# Simultaneous_RFID_Tag_Reader.net
KiCad netlist of a schematic drawn in EAGLE
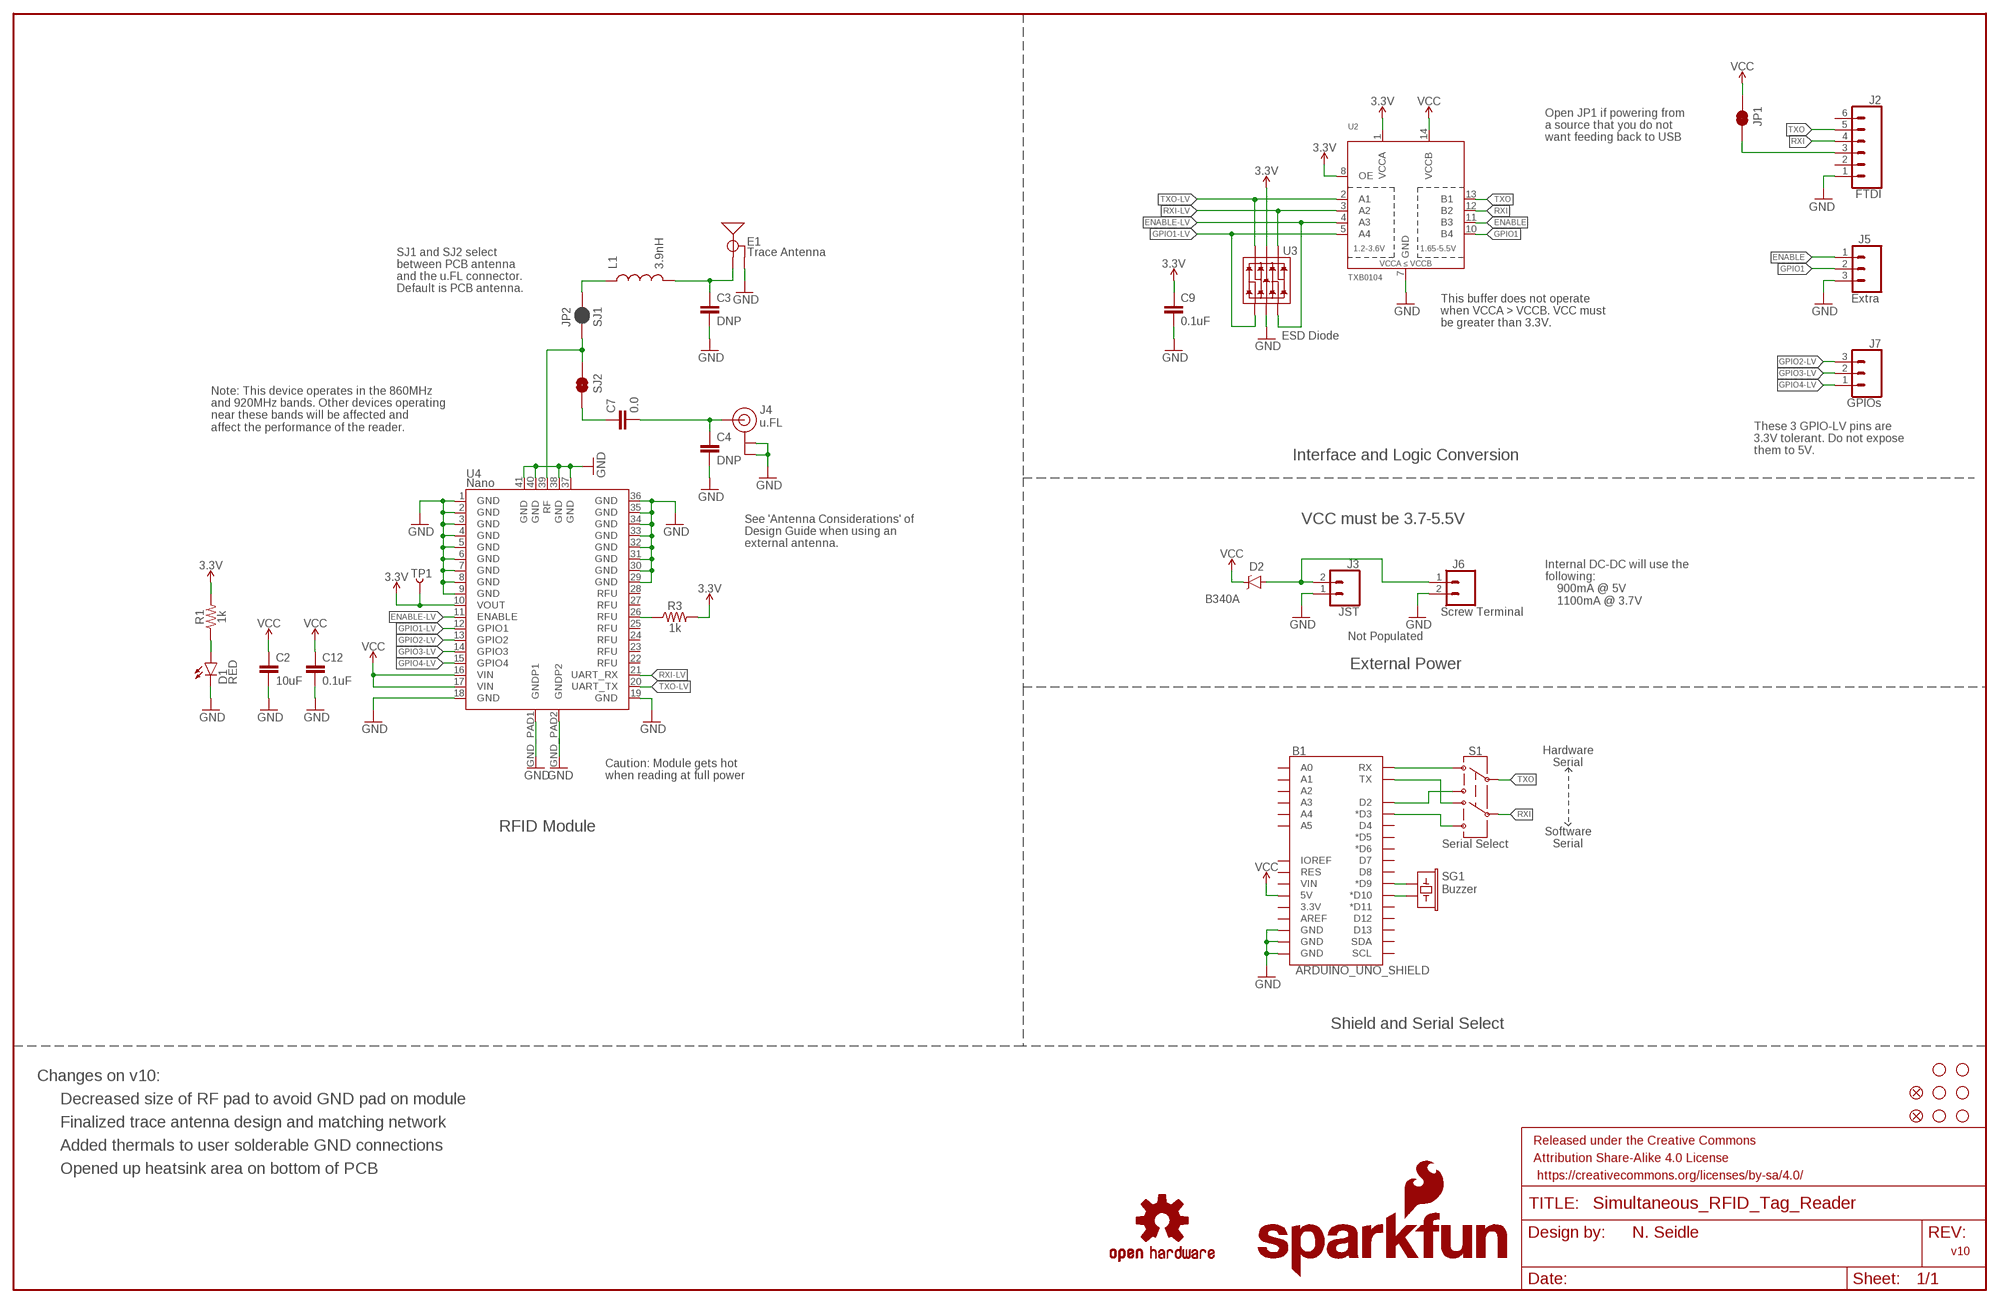
[diagram p0: schematic, sheet 1]

(export (version "E")
  (design (tool "Eeschema 10.0.6"))
  (components
    (comp (ref "B1")
      (value "ARDUINO_UNO_SHIELD")
      (footprint "eagle-import:UNO_R3_SHIELD")
      (libsource (lib "eagle-import") (part "ARDUINO_UNO_R3_SHIELDBASIC"))
    )
    (comp (ref "C2")
      (value "10uF")
      (footprint "eagle-import:0805")
      (libsource (lib "eagle-import") (part "10UF-0805-10V-10%"))
    )
    (comp (ref "C3")
      (value "DNP")
      (footprint "eagle-import:0603")
      (libsource (lib "eagle-import") (part "1.0PF-0603-50V-25%"))
    )
    (comp (ref "C4")
      (value "DNP")
      (footprint "eagle-import:0603")
      (libsource (lib "eagle-import") (part "1.0PF-0603-50V-25%"))
    )
    (comp (ref "C7")
      (value "0.0")
      (footprint "eagle-import:0603")
      (libsource (lib "eagle-import") (part "1.0PF-0603-50V-25%"))
    )
    (comp (ref "C9")
      (value "0.1uF")
      (footprint "eagle-import:0603")
      (libsource (lib "eagle-import") (part "0.1UF-0603-25V-(+80/-20%)"))
    )
    (comp (ref "C12")
      (value "0.1uF")
      (footprint "eagle-import:0603")
      (libsource (lib "eagle-import") (part "0.1UF-0603-25V-(+80/-20%)"))
    )
    (comp (ref "D1")
      (value "RED")
      (footprint "eagle-import:LED-0603")
      (libsource (lib "eagle-import") (part "LED-RED0603"))
    )
    (comp (ref "D2")
      (value "B340A")
      (footprint "eagle-import:SMA-DIODE")
      (libsource (lib "eagle-import") (part "DIODE-SCHOTTKY-B340A"))
    )
    (comp (ref "E1")
      (value "Trace Antenna")
      (footprint "eagle-import:915MHZ_ANTENNA_TRIMBLE")
      (libsource (lib "eagle-import") (part "ANTENNA_GROUNDED1"))
    )
    (comp (ref "FID1")
      (value "FIDUCIAL1X2")
      (footprint "eagle-import:FIDUCIAL-1X2")
      (libsource (lib "eagle-import") (part "FIDUCIAL1X2"))
    )
    (comp (ref "FID2")
      (value "FIDUCIAL1X2")
      (footprint "eagle-import:FIDUCIAL-1X2")
      (libsource (lib "eagle-import") (part "FIDUCIAL1X2"))
    )
    (comp (ref "FRAME1")
      (value "FRAME-LEDGER")
      (footprint "eagle-import:CREATIVE_COMMONS")
      (libsource (lib "eagle-import") (part "FRAME-LEDGER"))
    )
    (comp (ref "J2")
      (value "FTDI")
      (footprint "eagle-import:1X06")
      (libsource (lib "eagle-import") (part "CONN_06SILK_FEMALE_PTH"))
    )
    (comp (ref "J3")
      (value "JST")
      (footprint "eagle-import:JST-2-PTH")
      (libsource (lib "eagle-import") (part "CONN_02JST-PTH-2"))
    )
    (comp (ref "J4")
      (value "U.FL")
      (footprint "eagle-import:U.FL")
      (libsource (lib "eagle-import") (part "U.FL"))
    )
    (comp (ref "J5")
      (value "Extra")
      (footprint "eagle-import:1X03")
      (libsource (lib "eagle-import") (part "CONN_03"))
    )
    (comp (ref "J6")
      (value "Screw Terminal")
      (footprint "eagle-import:SCREWTERMINAL-3.5MM-2")
      (libsource (lib "eagle-import") (part "CONN_023.5MM"))
    )
    (comp (ref "J7")
      (value "GPIOs")
      (footprint "eagle-import:1X03")
      (libsource (lib "eagle-import") (part "CONN_03"))
    )
    (comp (ref "JP1")
      (value "JUMPER-SMT_2_NC_TRACE_SILK")
      (footprint "eagle-import:SMT-JUMPER_2_NC_TRACE_SILK")
      (libsource (lib "eagle-import") (part "JUMPER-SMT_2_NC_TRACE_SILK"))
    )
    (comp (ref "JP2")
      (value "SJ1")
      (footprint "eagle-import:SMT-JUMPER_2_NO_NO-SILK")
      (libsource (lib "eagle-import") (part "JUMPER-SMT_2_NO_NO-SILK"))
    )
    (comp (ref "L1")
      (value "3.9nH")
      (footprint "eagle-import:0603")
      (libsource (lib "eagle-import") (part "3.9NH_-+0.3NH_300MA(0603)0603"))
    )
    (comp (ref "LOGO1")
      (value "SFE_LOGO_NAME_FLAME.1_INCH")
      (footprint "eagle-import:SFE_LOGO_NAME_FLAME_.1")
      (libsource (lib "eagle-import") (part "SFE_LOGO_NAME_FLAME.1_INCH"))
    )
    (comp (ref "LOGO2")
      (value "OSHW-LOGOS")
      (footprint "eagle-import:OSHW-LOGO-S")
      (libsource (lib "eagle-import") (part "OSHW-LOGOS"))
    )
    (comp (ref "LOGO3")
      (value "SFE_LOGO_NAME_FLAME.1_INCH")
      (footprint "eagle-import:SFE_LOGO_NAME_FLAME_.1")
      (libsource (lib "eagle-import") (part "SFE_LOGO_NAME_FLAME.1_INCH"))
    )
    (comp (ref "R1")
      (value "1k")
      (footprint "eagle-import:0603")
      (libsource (lib "eagle-import") (part "1KOHM-0603-1/10W-1%"))
    )
    (comp (ref "R3")
      (value "1k")
      (footprint "eagle-import:0603")
      (libsource (lib "eagle-import") (part "1KOHM-0603-1/10W-1%"))
    )
    (comp (ref "S1")
      (value "Serial Select")
      (footprint "eagle-import:SWITCH_DPDT_SMD_AYZ0202")
      (libsource (lib "eagle-import") (part "SWITCH-DPDT-SMD-AYZ0202"))
    )
    (comp (ref "SG1")
      (value "Buzzer")
      (footprint "eagle-import:BUZZER-CCV")
      (libsource (lib "eagle-import") (part "BUZZERSMD2"))
    )
    (comp (ref "SJ2")
      (value "JUMPER-SMT_2_NO_NO-SILK")
      (footprint "eagle-import:SMT-JUMPER_2_NO_NO-SILK")
      (libsource (lib "eagle-import") (part "JUMPER-SMT_2_NO_NO-SILK"))
    )
    (comp (ref "STANDOFF1")
      (value "STAND-OFF")
      (footprint "eagle-import:STAND-OFF")
      (libsource (lib "eagle-import") (part "STAND-OFF"))
    )
    (comp (ref "STANDOFF2")
      (value "STAND-OFF")
      (footprint "eagle-import:STAND-OFF")
      (libsource (lib "eagle-import") (part "STAND-OFF"))
    )
    (comp (ref "STANDOFF3")
      (value "STAND-OFF")
      (footprint "eagle-import:STAND-OFF")
      (libsource (lib "eagle-import") (part "STAND-OFF"))
    )
    (comp (ref "STANDOFF4")
      (value "STAND-OFF")
      (footprint "eagle-import:STAND-OFF")
      (libsource (lib "eagle-import") (part "STAND-OFF"))
    )
    (comp (ref "STANDOFF7")
      (value "STAND-OFF")
      (footprint "eagle-import:STAND-OFF")
      (libsource (lib "eagle-import") (part "STAND-OFF"))
    )
    (comp (ref "STANDOFF8")
      (value "STAND-OFF")
      (footprint "eagle-import:STAND-OFF")
      (libsource (lib "eagle-import") (part "STAND-OFF"))
    )
    (comp (ref "TP1")
      (value "TEST-POINT3")
      (footprint "eagle-import:PAD.03X.03")
      (libsource (lib "eagle-import") (part "TEST-POINT3"))
    )
    (comp (ref "U2")
      (value "TXB0104")
      (footprint "eagle-import:SO14")
      (libsource (lib "eagle-import") (part "TXB0104PWRSOIC14"))
    )
    (comp (ref "U3")
      (value "ESD Diode")
      (footprint "eagle-import:SOT-23-6")
      (libsource (lib "eagle-import") (part "TVS_DIODE_ARRAYSMD"))
    )
    (comp (ref "U4")
      (value "Nano")
      (footprint "eagle-import:NANO_MODULE")
      (libsource (lib "eagle-import") (part "UHF_RFID_NANO_MODULE"))
    )
  )
  (nets
    (net (code "1") (name "3.3V") (class "Default")
      (node (ref "C9") (pin "1") (pinfunction "1_1") (pintype "passive"))
      (node (ref "R1") (pin "2") (pinfunction "2_2") (pintype "passive"))
      (node (ref "R3") (pin "2") (pinfunction "2_2") (pintype "passive"))
      (node (ref "TP1") (pin "P$1") (pinfunction "1_P$1") (pintype "bidirectional"))
      (node (ref "U2") (pin "1") (pinfunction "VCCA_1") (pintype "bidirectional"))
      (node (ref "U2") (pin "8") (pinfunction "OE_8") (pintype "bidirectional"))
      (node (ref "U3") (pin "5") (pinfunction "VCC_5") (pintype "bidirectional"))
      (node (ref "U4") (pin "10") (pinfunction "VOUT_10") (pintype "bidirectional"))
    )
    (net (code "2") (name "ENABLE") (class "Default")
      (node (ref "J5") (pin "1") (pinfunction "1_1") (pintype "passive"))
      (node (ref "U2") (pin "11") (pinfunction "B3_11") (pintype "bidirectional"))
    )
    (net (code "3") (name "ENABLE-LV") (class "Default")
      (node (ref "U2") (pin "4") (pinfunction "A3_4") (pintype "bidirectional"))
      (node (ref "U3") (pin "3") (pinfunction "IO2_3") (pintype "bidirectional"))
      (node (ref "U4") (pin "11") (pinfunction "ENABLE_11") (pintype "bidirectional"))
    )
    (net (code "4") (name "GND") (class "Default")
      (node (ref "B1") (pin "GND@0") (pinfunction "GND_GND@0") (pintype "bidirectional"))
      (node (ref "B1") (pin "GND@1") (pinfunction "GND_GND@1") (pintype "bidirectional"))
      (node (ref "B1") (pin "GND@2") (pinfunction "GND_GND@2") (pintype "bidirectional"))
      (node (ref "C12") (pin "2") (pinfunction "2_2") (pintype "passive"))
      (node (ref "C2") (pin "2") (pinfunction "2_2") (pintype "passive"))
      (node (ref "C3") (pin "2") (pinfunction "2_2") (pintype "passive"))
      (node (ref "C4") (pin "2") (pinfunction "2_2") (pintype "passive"))
      (node (ref "C9") (pin "2") (pinfunction "2_2") (pintype "passive"))
      (node (ref "D1") (pin "C") (pinfunction "C_C") (pintype "passive"))
      (node (ref "E1") (pin "GND@1") (pinfunction "GND_GND@1") (pintype "bidirectional"))
      (node (ref "E1") (pin "GND@2") (pinfunction "GND_GND@2") (pintype "bidirectional"))
      (node (ref "E1") (pin "GND@3") (pinfunction "GND_GND@3") (pintype "bidirectional"))
      (node (ref "J2") (pin "1") (pinfunction "1_1") (pintype "passive"))
      (node (ref "J3") (pin "1") (pinfunction "1_1") (pintype "passive"))
      (node (ref "J4") (pin "P$1") (pinfunction "GND_P$1") (pintype "bidirectional"))
      (node (ref "J4") (pin "P$2") (pinfunction "GND_P$2") (pintype "bidirectional"))
      (node (ref "J5") (pin "3") (pinfunction "3_3") (pintype "passive"))
      (node (ref "J6") (pin "2") (pinfunction "2_2") (pintype "passive"))
      (node (ref "U2") (pin "7") (pinfunction "GND_7") (pintype "bidirectional"))
      (node (ref "U3") (pin "2") (pinfunction "VSS_2") (pintype "bidirectional"))
      (node (ref "U4") (pin "1") (pinfunction "GND_1") (pintype "bidirectional"))
      (node (ref "U4") (pin "18") (pinfunction "GND_18") (pintype "bidirectional"))
      (node (ref "U4") (pin "19") (pinfunction "GND_19") (pintype "bidirectional"))
      (node (ref "U4") (pin "2") (pinfunction "GND_2") (pintype "bidirectional"))
      (node (ref "U4") (pin "29") (pinfunction "GND_29") (pintype "bidirectional"))
      (node (ref "U4") (pin "3") (pinfunction "GND_3") (pintype "bidirectional"))
      (node (ref "U4") (pin "30") (pinfunction "GND_30") (pintype "bidirectional"))
      (node (ref "U4") (pin "31") (pinfunction "GND_31") (pintype "bidirectional"))
      (node (ref "U4") (pin "32") (pinfunction "GND_32") (pintype "bidirectional"))
      (node (ref "U4") (pin "33") (pinfunction "GND_33") (pintype "bidirectional"))
      (node (ref "U4") (pin "34") (pinfunction "GND_34") (pintype "bidirectional"))
      (node (ref "U4") (pin "35") (pinfunction "GND_35") (pintype "bidirectional"))
      (node (ref "U4") (pin "36") (pinfunction "GND_36") (pintype "bidirectional"))
      (node (ref "U4") (pin "37") (pinfunction "GND_37") (pintype "bidirectional"))
      (node (ref "U4") (pin "38") (pinfunction "GND_38") (pintype "bidirectional"))
      (node (ref "U4") (pin "4") (pinfunction "GND_4") (pintype "bidirectional"))
      (node (ref "U4") (pin "40") (pinfunction "GND_40") (pintype "bidirectional"))
      (node (ref "U4") (pin "41") (pinfunction "GND_41") (pintype "bidirectional"))
      (node (ref "U4") (pin "5") (pinfunction "GND_5") (pintype "bidirectional"))
      (node (ref "U4") (pin "6") (pinfunction "GND_6") (pintype "bidirectional"))
      (node (ref "U4") (pin "7") (pinfunction "GND_7") (pintype "bidirectional"))
      (node (ref "U4") (pin "8") (pinfunction "GND_8") (pintype "bidirectional"))
      (node (ref "U4") (pin "9") (pinfunction "GND_9") (pintype "bidirectional"))
      (node (ref "U4") (pin "GND_PAD1") (pinfunction "GNDP1_GND_PAD1") (pintype "bidirectional"))
      (node (ref "U4") (pin "GND_PAD2") (pinfunction "GNDP2_GND_PAD2") (pintype "bidirectional"))
    )
    (net (code "5") (name "GPIO1") (class "Default")
      (node (ref "J5") (pin "2") (pinfunction "2_2") (pintype "passive"))
      (node (ref "U2") (pin "10") (pinfunction "B4_10") (pintype "bidirectional"))
    )
    (net (code "6") (name "GPIO1-LV") (class "Default")
      (node (ref "U2") (pin "5") (pinfunction "A4_5") (pintype "bidirectional"))
      (node (ref "U3") (pin "1") (pinfunction "IO1_1") (pintype "bidirectional"))
      (node (ref "U4") (pin "12") (pinfunction "GPIO1_12") (pintype "bidirectional"))
    )
    (net (code "7") (name "GPIO2-LV") (class "Default")
      (node (ref "J7") (pin "3") (pinfunction "3_3") (pintype "passive"))
      (node (ref "U4") (pin "13") (pinfunction "GPIO2_13") (pintype "bidirectional"))
    )
    (net (code "8") (name "GPIO3-LV") (class "Default")
      (node (ref "J7") (pin "2") (pinfunction "2_2") (pintype "passive"))
      (node (ref "U4") (pin "14") (pinfunction "GPIO3_14") (pintype "bidirectional"))
    )
    (net (code "9") (name "GPIO4-LV") (class "Default")
      (node (ref "J7") (pin "1") (pinfunction "1_1") (pintype "passive"))
      (node (ref "U4") (pin "15") (pinfunction "GPIO4_15") (pintype "bidirectional"))
    )
    (net (code "10") (name "Net-(B1-*D3)") (class "Default")
      (node (ref "B1") (pin "D3") (pinfunction "*D3_D3") (pintype "bidirectional"))
      (node (ref "S1") (pin "6") (pinfunction "6_6") (pintype "bidirectional"))
    )
    (net (code "11") (name "Net-(B1-*D9)") (class "Default")
      (node (ref "B1") (pin "D9") (pinfunction "*D9_D9") (pintype "bidirectional"))
      (node (ref "SG1") (pin "+") (pinfunction "1_+") (pintype "passive"))
    )
    (net (code "12") (name "Net-(B1-*D10)") (class "Default")
      (node (ref "B1") (pin "D10") (pinfunction "*D10_D10") (pintype "bidirectional"))
      (node (ref "SG1") (pin "-") (pinfunction "2_-") (pintype "passive"))
    )
    (net (code "13") (name "Net-(B1-PadD2)") (class "Default")
      (node (ref "B1") (pin "D2") (pinfunction "D2_D2") (pintype "bidirectional"))
      (node (ref "S1") (pin "3") (pinfunction "3_3") (pintype "bidirectional"))
    )
    (net (code "14") (name "Net-(B1-PadRX)") (class "Default")
      (node (ref "B1") (pin "RX") (pinfunction "RX_RX") (pintype "bidirectional"))
      (node (ref "S1") (pin "1") (pinfunction "1_1") (pintype "bidirectional"))
    )
    (net (code "15") (name "Net-(B1-PadTX)") (class "Default")
      (node (ref "B1") (pin "TX") (pinfunction "TX_TX") (pintype "bidirectional"))
      (node (ref "S1") (pin "4") (pinfunction "4_4") (pintype "bidirectional"))
    )
    (net (code "16") (name "Net-(C7-Pad1)") (class "Default")
      (node (ref "C7") (pin "1") (pinfunction "1_1") (pintype "passive"))
      (node (ref "SJ2") (pin "2") (pinfunction "2_2") (pintype "passive"))
    )
    (net (code "17") (name "Net-(D1-PadA)") (class "Default")
      (node (ref "D1") (pin "A") (pinfunction "A_A") (pintype "passive"))
      (node (ref "R1") (pin "1") (pinfunction "1_1") (pintype "passive"))
    )
    (net (code "18") (name "Net-(D2-PadA)") (class "Default")
      (node (ref "D2") (pin "A") (pinfunction "A_A") (pintype "passive"))
      (node (ref "J3") (pin "2") (pinfunction "2_2") (pintype "passive"))
      (node (ref "J6") (pin "1") (pinfunction "1_1") (pintype "passive"))
    )
    (net (code "19") (name "Net-(E1-SIGNAL)") (class "Default")
      (node (ref "C3") (pin "1") (pinfunction "1_1") (pintype "passive"))
      (node (ref "E1") (pin "ANT") (pinfunction "SIGNAL_ANT") (pintype "bidirectional"))
      (node (ref "L1") (pin "2") (pinfunction "2_2") (pintype "passive"))
    )
    (net (code "20") (name "Net-(J2-Pad3)") (class "Default")
      (node (ref "J2") (pin "3") (pinfunction "3_3") (pintype "passive"))
      (node (ref "JP1") (pin "2") (pinfunction "2_2") (pintype "passive"))
    )
    (net (code "21") (name "Net-(J4-SIGNAL)") (class "Default")
      (node (ref "C4") (pin "1") (pinfunction "1_1") (pintype "passive"))
      (node (ref "C7") (pin "2") (pinfunction "2_2") (pintype "passive"))
      (node (ref "J4") (pin "P$3") (pinfunction "SIGNAL_P$3") (pintype "bidirectional"))
    )
    (net (code "22") (name "Net-(JP2-Pad2)") (class "Default")
      (node (ref "JP2") (pin "2") (pinfunction "2_2") (pintype "passive"))
      (node (ref "L1") (pin "1") (pinfunction "1_1") (pintype "passive"))
    )
    (net (code "23") (name "Net-(R3-Pad1)") (class "Default")
      (node (ref "R3") (pin "1") (pinfunction "1_1") (pintype "passive"))
      (node (ref "U4") (pin "26") (pinfunction "RFU_26") (pintype "bidirectional"))
    )
    (net (code "24") (name "Net-(U4-RF)") (class "Default")
      (node (ref "JP2") (pin "1") (pinfunction "1_1") (pintype "passive"))
      (node (ref "SJ2") (pin "1") (pinfunction "1_1") (pintype "passive"))
      (node (ref "U4") (pin "39") (pinfunction "RF_39") (pintype "bidirectional"))
    )
    (net (code "25") (name "RXI") (class "Default")
      (node (ref "J2") (pin "4") (pinfunction "4_4") (pintype "passive"))
      (node (ref "S1") (pin "5") (pinfunction "5_5") (pintype "bidirectional"))
      (node (ref "U2") (pin "12") (pinfunction "B2_12") (pintype "bidirectional"))
    )
    (net (code "26") (name "RXI-LV") (class "Default")
      (node (ref "U2") (pin "3") (pinfunction "A2_3") (pintype "bidirectional"))
      (node (ref "U3") (pin "4") (pinfunction "IO3_4") (pintype "bidirectional"))
      (node (ref "U4") (pin "21") (pinfunction "UART_RX_21") (pintype "bidirectional"))
    )
    (net (code "27") (name "TXO") (class "Default")
      (node (ref "J2") (pin "5") (pinfunction "5_5") (pintype "passive"))
      (node (ref "S1") (pin "2") (pinfunction "2_2") (pintype "bidirectional"))
      (node (ref "U2") (pin "13") (pinfunction "B1_13") (pintype "bidirectional"))
    )
    (net (code "28") (name "TXO-LV") (class "Default")
      (node (ref "U2") (pin "2") (pinfunction "A1_2") (pintype "bidirectional"))
      (node (ref "U3") (pin "6") (pinfunction "IO4_6") (pintype "bidirectional"))
      (node (ref "U4") (pin "20") (pinfunction "UART_TX_20") (pintype "bidirectional"))
    )
    (net (code "29") (name "VCC") (class "Default")
      (node (ref "B1") (pin "5V") (pinfunction "5V_5V") (pintype "bidirectional"))
      (node (ref "C12") (pin "1") (pinfunction "1_1") (pintype "passive"))
      (node (ref "C2") (pin "1") (pinfunction "1_1") (pintype "passive"))
      (node (ref "D2") (pin "C") (pinfunction "C_C") (pintype "passive"))
      (node (ref "JP1") (pin "1") (pinfunction "1_1") (pintype "passive"))
      (node (ref "U2") (pin "14") (pinfunction "VCCB_14") (pintype "bidirectional"))
      (node (ref "U4") (pin "16") (pinfunction "VIN_16") (pintype "bidirectional"))
      (node (ref "U4") (pin "17") (pinfunction "VIN_17") (pintype "bidirectional"))
    )
    (net (code "30") (name "unconnected-(B1-*D5-PadD5)") (class "Default")
      (node (ref "B1") (pin "D5") (pinfunction "*D5_D5") (pintype "bidirectional"))
    )
    (net (code "31") (name "unconnected-(B1-*D6-PadD6)") (class "Default")
      (node (ref "B1") (pin "D6") (pinfunction "*D6_D6") (pintype "bidirectional"))
    )
    (net (code "32") (name "unconnected-(B1-*D11-PadD11)") (class "Default")
      (node (ref "B1") (pin "D11") (pinfunction "*D11_D11") (pintype "bidirectional"))
    )
    (net (code "33") (name "unconnected-(B1-Pad3.3V)") (class "Default")
      (node (ref "B1") (pin "3.3V") (pinfunction "3.3V_3.3V") (pintype "bidirectional"))
    )
    (net (code "34") (name "unconnected-(B1-PadA0)") (class "Default")
      (node (ref "B1") (pin "A0") (pinfunction "A0_A0") (pintype "bidirectional"))
    )
    (net (code "35") (name "unconnected-(B1-PadA1)") (class "Default")
      (node (ref "B1") (pin "A1") (pinfunction "A1_A1") (pintype "bidirectional"))
    )
    (net (code "36") (name "unconnected-(B1-PadA2)") (class "Default")
      (node (ref "B1") (pin "A2") (pinfunction "A2_A2") (pintype "bidirectional"))
    )
    (net (code "37") (name "unconnected-(B1-PadA3)") (class "Default")
      (node (ref "B1") (pin "A3") (pinfunction "A3_A3") (pintype "bidirectional"))
    )
    (net (code "38") (name "unconnected-(B1-PadA4)") (class "Default")
      (node (ref "B1") (pin "A4") (pinfunction "A4_A4") (pintype "bidirectional"))
    )
    (net (code "39") (name "unconnected-(B1-PadA5)") (class "Default")
      (node (ref "B1") (pin "A5") (pinfunction "A5_A5") (pintype "bidirectional"))
    )
    (net (code "40") (name "unconnected-(B1-PadAREF)") (class "Default")
      (node (ref "B1") (pin "AREF") (pinfunction "AREF_AREF") (pintype "bidirectional"))
    )
    (net (code "41") (name "unconnected-(B1-PadD4)") (class "Default")
      (node (ref "B1") (pin "D4") (pinfunction "D4_D4") (pintype "bidirectional"))
    )
    (net (code "42") (name "unconnected-(B1-PadD7)") (class "Default")
      (node (ref "B1") (pin "D7") (pinfunction "D7_D7") (pintype "bidirectional"))
    )
    (net (code "43") (name "unconnected-(B1-PadD8)") (class "Default")
      (node (ref "B1") (pin "D8") (pinfunction "D8_D8") (pintype "bidirectional"))
    )
    (net (code "44") (name "unconnected-(B1-PadD12)") (class "Default")
      (node (ref "B1") (pin "D12") (pinfunction "D12_D12") (pintype "bidirectional"))
    )
    (net (code "45") (name "unconnected-(B1-PadD13)") (class "Default")
      (node (ref "B1") (pin "D13") (pinfunction "D13_D13") (pintype "bidirectional"))
    )
    (net (code "46") (name "unconnected-(B1-PadIOREF)") (class "Default")
      (node (ref "B1") (pin "IOREF") (pinfunction "IOREF_IOREF") (pintype "bidirectional"))
    )
    (net (code "47") (name "unconnected-(B1-PadRES)") (class "Default")
      (node (ref "B1") (pin "RES") (pinfunction "RES_RES") (pintype "bidirectional"))
    )
    (net (code "48") (name "unconnected-(B1-PadSCL)") (class "Default")
      (node (ref "B1") (pin "SCL") (pinfunction "SCL_SCL") (pintype "bidirectional"))
    )
    (net (code "49") (name "unconnected-(B1-PadSDA)") (class "Default")
      (node (ref "B1") (pin "SDA") (pinfunction "SDA_SDA") (pintype "bidirectional"))
    )
    (net (code "50") (name "unconnected-(B1-PadVIN)") (class "Default")
      (node (ref "B1") (pin "VIN") (pinfunction "VIN_VIN") (pintype "bidirectional"))
    )
    (net (code "51") (name "unconnected-(J2-Pad2)") (class "Default")
      (node (ref "J2") (pin "2") (pinfunction "2_2") (pintype "passive"))
    )
    (net (code "52") (name "unconnected-(J2-Pad6)") (class "Default")
      (node (ref "J2") (pin "6") (pinfunction "6_6") (pintype "passive"))
    )
    (net (code "53") (name "unconnected-(U4-RFU-Pad22)") (class "Default")
      (node (ref "U4") (pin "22") (pinfunction "RFU_22") (pintype "bidirectional"))
    )
    (net (code "54") (name "unconnected-(U4-RFU-Pad23)") (class "Default")
      (node (ref "U4") (pin "23") (pinfunction "RFU_23") (pintype "bidirectional"))
    )
    (net (code "55") (name "unconnected-(U4-RFU-Pad24)") (class "Default")
      (node (ref "U4") (pin "24") (pinfunction "RFU_24") (pintype "bidirectional"))
    )
    (net (code "56") (name "unconnected-(U4-RFU-Pad25)") (class "Default")
      (node (ref "U4") (pin "25") (pinfunction "RFU_25") (pintype "bidirectional"))
    )
    (net (code "57") (name "unconnected-(U4-RFU-Pad27)") (class "Default")
      (node (ref "U4") (pin "27") (pinfunction "RFU_27") (pintype "bidirectional"))
    )
    (net (code "58") (name "unconnected-(U4-RFU-Pad28)") (class "Default")
      (node (ref "U4") (pin "28") (pinfunction "RFU_28") (pintype "bidirectional"))
    )
  )
)
